# SALIDA_RF.net
KiCad netlist of a schematic drawn in Altium Designer
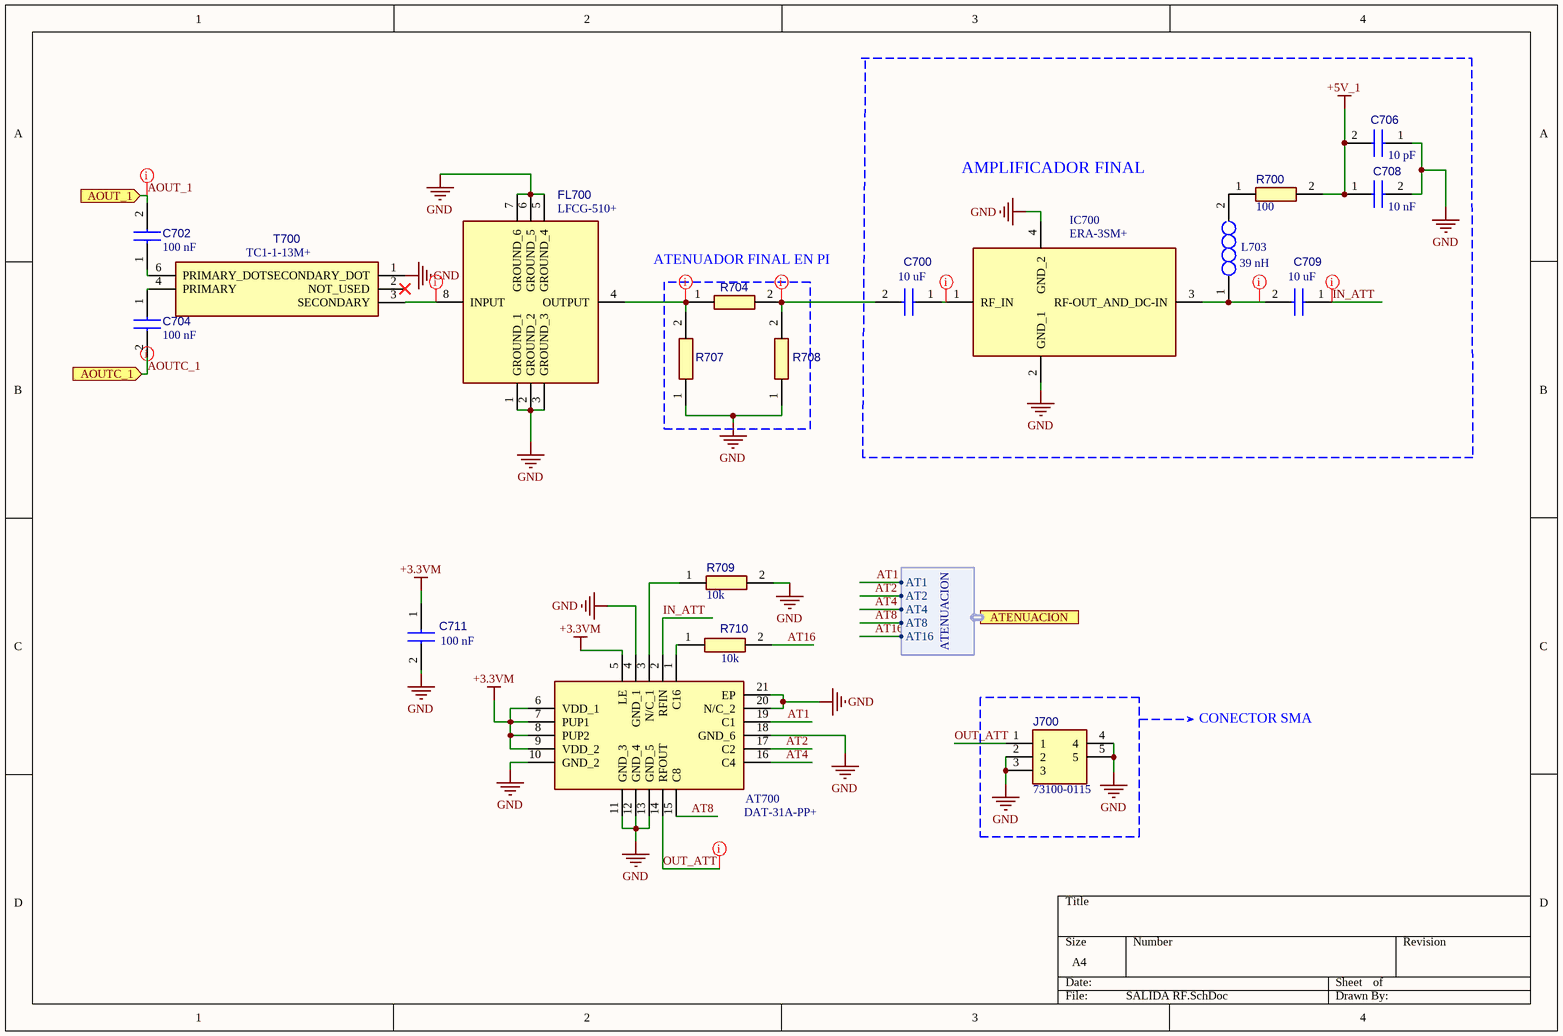
[diagram p0: SALIDA RF.SchDoc]

(export (version "E")
  (design (tool "Eeschema 10.0.6"))
  (components
    (comp (ref "AT700")
      (value "DAT-31A-PP+")
      (footprint "SamacSys:QFN50P400X400X85-21N")
      (description "Attenuator or Isolator")
      (fields (field (name "MOUSER PART NUMBER") "139-DAT-31A-PP+"))
      (libsource (lib "SamacSys") (part "DAT-31A-PP+"))
    )
    (comp (ref "C700")
      (value "10 uF")
      (footprint "SamacSys:C0603")
      (description "Capacitor")
      (fields (field (name "MANUFACTURER_PART_NUMBER") "C0603H470J5GACTU"))
      (libsource (lib "*") (part "C0603H470J5GACTU"))
    )
    (comp (ref "C702")
      (value "100 nF")
      (footprint "SamacSys:C0603")
      (description "Capacitor")
      (fields (field (name "MANUFACTURER_PART_NUMBER") "C0603H470J5GACTU"))
      (libsource (lib "*") (part "C0603H470J5GACTU"))
    )
    (comp (ref "C704")
      (value "100 nF")
      (footprint "SamacSys:C0603")
      (description "Capacitor")
      (fields (field (name "MANUFACTURER_PART_NUMBER") "C0603H470J5GACTU"))
      (libsource (lib "*") (part "C0603H470J5GACTU"))
    )
    (comp (ref "C706")
      (value "10 pF")
      (footprint "SamacSys:C0603")
      (description "Capacitor")
      (fields (field (name "MANUFACTURER_PART_NUMBER") "C0603H470J5GACTU"))
      (libsource (lib "*") (part "C0603H470J5GACTU"))
    )
    (comp (ref "C708")
      (value "10 nF")
      (footprint "SamacSys:C0603")
      (description "Capacitor")
      (fields (field (name "MANUFACTURER_PART_NUMBER") "C0603H470J5GACTU"))
      (libsource (lib "*") (part "C0603H470J5GACTU"))
    )
    (comp (ref "C709")
      (value "10 uF")
      (footprint "SamacSys:C0603")
      (description "Capacitor")
      (fields (field (name "MANUFACTURER_PART_NUMBER") "C0603H470J5GACTU"))
      (libsource (lib "*") (part "C0603H470J5GACTU"))
    )
    (comp (ref "C711")
      (value "100 nF")
      (footprint "SamacSys:C0603")
      (description "Capacitor")
      (fields (field (name "MANUFACTURER_PART_NUMBER") "C0603H470J5GACTU"))
      (libsource (lib "*") (part "C0603H470J5GACTU"))
    )
    (comp (ref "FL700")
      (value "LFCG-510+")
      (footprint "SamacSys:LFCG2000")
      (description "Filter")
      (fields
        (field (name "MANUFACTURER_PART_NUMBER") "LFCG-2000+")
        (field (name "MOUSER PART NUMBER") "139-LFCG-2000+")
      )
      (libsource (lib "*") (part "LFCG-2000+"))
    )
    (comp (ref "IC700")
      (value "ERA-3SM+")
      (footprint "SamacSys:ERA3SM")
      (description "Integrated Circuit")
      (fields (field (name "MOUSER PART NUMBER") "139-ERA-3SM"))
      (libsource (lib "*") (part "ERA-3SM+"))
    )
    (comp (ref "J700")
      (value "73100-0115")
      (footprint "SamacSys:731000115")
      (description "Connector")
      (fields (field (name "MOUSER PART NUMBER") "538-73100-0115"))
      (libsource (lib "*") (part "73100-0115"))
    )
    (comp (ref "L703")
      (value "39 nH")
      (footprint "SamacSys:INDC1608X95N")
      (description "Inductor")
      (fields
        (field (name "MANUFACTURER_PART_NUMBER") "AIML-0603-100K-T")
        (field (name "MOUSER PART NUMBER") "815-AIML-0603-100KT")
      )
      (libsource (lib "*") (part "AIML-0603-100K-T"))
    )
    (comp (ref "R700")
      (value "100")
      (footprint "SamacSys:RESC1608X55N")
      (description "Resistor")
      (fields
        (field (name "MANUFACTURER_PART_NUMBER") "CR0603-FX-1431ELF")
        (field (name "MOUSER PART NUMBER") "652-CR0603FX-1431ELF")
      )
      (libsource (lib "*") (part "CR0603-FX-1431ELF"))
    )
    (comp (ref "R704")
      (value "0")
      (footprint "SamacSys:RESC1608X55N")
      (description "Resistor")
      (fields
        (field (name "MANUFACTURER_PART_NUMBER") "CR0603-FX-1431ELF")
        (field (name "MOUSER PART NUMBER") "652-CR0603FX-1431ELF")
      )
      (libsource (lib "*") (part "CR0603-FX-1431ELF"))
    )
    (comp (ref "R707")
      (value "ATENUADOR")
      (footprint "SamacSys:RESC1608X55N")
      (description "Resistor")
      (fields
        (field (name "MANUFACTURER_PART_NUMBER") "CR0603-FX-1431ELF")
        (field (name "MOUSER PART NUMBER") "652-CR0603FX-1431ELF")
      )
      (libsource (lib "") (part "CR0603-FX-1431ELF_1"))
    )
    (comp (ref "R708")
      (value "ATENUADOR")
      (footprint "SamacSys:RESC1608X55N")
      (description "Resistor")
      (fields
        (field (name "MANUFACTURER_PART_NUMBER") "CR0603-FX-1431ELF")
        (field (name "MOUSER PART NUMBER") "652-CR0603FX-1431ELF")
      )
      (libsource (lib "") (part "CR0603-FX-1431ELF_1"))
    )
    (comp (ref "R709")
      (value "10k")
      (footprint "SamacSys:RESC1608X55N")
      (description "Resistor")
      (fields
        (field (name "MANUFACTURER_PART_NUMBER") "CR0603-FX-1431ELF")
        (field (name "MOUSER PART NUMBER") "652-CR0603FX-1431ELF")
      )
      (libsource (lib "*") (part "CR0603-FX-1431ELF"))
    )
    (comp (ref "R710")
      (value "10k")
      (footprint "SamacSys:RESC1608X55N")
      (description "Resistor")
      (fields
        (field (name "MANUFACTURER_PART_NUMBER") "CR0603-FX-1431ELF")
        (field (name "MOUSER PART NUMBER") "652-CR0603FX-1431ELF")
      )
      (libsource (lib "*") (part "CR0603-FX-1431ELF"))
    )
    (comp (ref "T700")
      (value "TC1-1-13M+")
      (footprint "SamacSys:TC414")
      (description "Transformer")
      (fields (field (name "MOUSER PART NUMBER") "139-TC1-1-13M"))
      (libsource (lib "*") (part "TC1-1-13M+"))
    )
  )
  (nets
    (net (code "2") (name "+3.3VM") (class "Default")
      (node (ref "AT700") (pin "5") (pinfunction "LE_5") (pintype "passive"))
      (node (ref "AT700") (pin "6") (pinfunction "VDD_1_6") (pintype "passive"))
      (node (ref "AT700") (pin "7") (pinfunction "PUP1_7") (pintype "passive"))
      (node (ref "AT700") (pin "8") (pinfunction "PUP2_8") (pintype "passive"))
      (node (ref "AT700") (pin "9") (pinfunction "VDD_2_9") (pintype "passive"))
      (node (ref "C711") (pin "1") (pinfunction "1_1") (pintype "passive"))
    )
    (net (code "3") (name "+5V_1") (class "Default")
      (node (ref "C706") (pin "2") (pinfunction "2_2") (pintype "passive"))
      (node (ref "C708") (pin "1") (pinfunction "1_1") (pintype "passive"))
      (node (ref "R700") (pin "2") (pinfunction "2_2") (pintype "passive"))
    )
    (net (code "4") (name "/AOUTC_1") (class "Default")
      (node (ref "C704") (pin "2") (pinfunction "2_2") (pintype "passive"))
    )
    (net (code "5") (name "/AOUT_1") (class "Default")
      (node (ref "C702") (pin "2") (pinfunction "2_2") (pintype "passive"))
    )
    (net (code "6") (name "/AT1") (class "Default")
      (node (ref "AT700") (pin "19") (pinfunction "C1_19") (pintype "passive"))
    )
    (net (code "7") (name "/AT2") (class "Default")
      (node (ref "AT700") (pin "17") (pinfunction "C2_17") (pintype "passive"))
    )
    (net (code "8") (name "/AT4") (class "Default")
      (node (ref "AT700") (pin "16") (pinfunction "C4_16") (pintype "passive"))
    )
    (net (code "9") (name "/AT8") (class "Default")
      (node (ref "AT700") (pin "15") (pinfunction "C8_15") (pintype "passive"))
    )
    (net (code "10") (name "/AT16") (class "Default")
      (node (ref "R710") (pin "2") (pinfunction "2_2") (pintype "passive"))
    )
    (net (code "11") (name "/IN_ATT") (class "Default")
      (node (ref "AT700") (pin "2") (pinfunction "RFIN_2") (pintype "passive"))
      (node (ref "C709") (pin "1") (pinfunction "1_1") (pintype "passive"))
    )
    (net (code "12") (name "/OUT_ATT") (class "Default")
      (node (ref "AT700") (pin "14") (pinfunction "RFOUT_14") (pintype "passive"))
      (node (ref "J700") (pin "1") (pinfunction "1_1") (pintype "passive"))
    )
    (net (code "14") (name "GND") (class "Default")
      (node (ref "AT700") (pin "10") (pinfunction "GND_2_10") (pintype "passive"))
      (node (ref "AT700") (pin "11") (pinfunction "GND_3_11") (pintype "passive"))
      (node (ref "AT700") (pin "12") (pinfunction "GND_4_12") (pintype "passive"))
      (node (ref "AT700") (pin "13") (pinfunction "GND_5_13") (pintype "passive"))
      (node (ref "AT700") (pin "18") (pinfunction "GND_6_18") (pintype "passive"))
      (node (ref "AT700") (pin "20") (pinfunction "N/C_2_20") (pintype "passive"))
      (node (ref "AT700") (pin "21") (pinfunction "EP_21") (pintype "passive"))
      (node (ref "AT700") (pin "4") (pinfunction "GND_1_4") (pintype "passive"))
      (node (ref "C706") (pin "1") (pinfunction "1_1") (pintype "passive"))
      (node (ref "C708") (pin "2") (pinfunction "2_2") (pintype "passive"))
      (node (ref "C711") (pin "2") (pinfunction "2_2") (pintype "passive"))
      (node (ref "FL700") (pin "1") (pinfunction "GROUND_1_1") (pintype "passive"))
      (node (ref "FL700") (pin "2") (pinfunction "GROUND_2_2") (pintype "passive"))
      (node (ref "FL700") (pin "3") (pinfunction "GROUND_3_3") (pintype "passive"))
      (node (ref "FL700") (pin "5") (pinfunction "GROUND_4_5") (pintype "passive"))
      (node (ref "FL700") (pin "6") (pinfunction "GROUND_5_6") (pintype "passive"))
      (node (ref "FL700") (pin "7") (pinfunction "GROUND_6_7") (pintype "passive"))
      (node (ref "IC700") (pin "2") (pinfunction "GND_1_2") (pintype "passive"))
      (node (ref "IC700") (pin "4") (pinfunction "GND_2_4") (pintype "passive"))
      (node (ref "J700") (pin "2") (pinfunction "2_2") (pintype "passive"))
      (node (ref "J700") (pin "3") (pinfunction "3_3") (pintype "passive"))
      (node (ref "J700") (pin "4") (pinfunction "4_4") (pintype "passive"))
      (node (ref "J700") (pin "5") (pinfunction "5_5") (pintype "passive"))
      (node (ref "R707") (pin "1") (pinfunction "1_1") (pintype "passive"))
      (node (ref "R708") (pin "1") (pinfunction "1_1") (pintype "passive"))
      (node (ref "R709") (pin "2") (pinfunction "2_2") (pintype "passive"))
      (node (ref "T700") (pin "1") (pinfunction "SECONDARY_DOT_1") (pintype "passive"))
    )
    (net (code "15") (name "Net-(AT700-C16)") (class "Default")
      (node (ref "AT700") (pin "1") (pinfunction "C16_1") (pintype "passive"))
      (node (ref "R710") (pin "1") (pinfunction "1_1") (pintype "passive"))
    )
    (net (code "16") (name "Net-(AT700-N{slash}C_1)") (class "Default")
      (node (ref "AT700") (pin "3") (pinfunction "N/C_1_3") (pintype "passive"))
      (node (ref "R709") (pin "1") (pinfunction "1_1") (pintype "passive"))
    )
    (net (code "17") (name "Net-(C700-Pad2)") (class "Default")
      (node (ref "C700") (pin "2") (pinfunction "2_2") (pintype "passive"))
      (node (ref "R704") (pin "2") (pinfunction "2_2") (pintype "passive"))
      (node (ref "R708") (pin "2") (pinfunction "2_2") (pintype "passive"))
    )
    (net (code "18") (name "Net-(FL700-INPUT)") (class "Default")
      (node (ref "FL700") (pin "8") (pinfunction "INPUT_8") (pintype "passive"))
      (node (ref "T700") (pin "3") (pinfunction "SECONDARY_3") (pintype "passive"))
    )
    (net (code "19") (name "Net-(FL700-OUTPUT)") (class "Default")
      (node (ref "FL700") (pin "4") (pinfunction "OUTPUT_4") (pintype "passive"))
      (node (ref "R704") (pin "1") (pinfunction "1_1") (pintype "passive"))
      (node (ref "R707") (pin "2") (pinfunction "2_2") (pintype "passive"))
    )
    (net (code "20") (name "Net-(IC700-RF-OUT_AND_DC-IN)") (class "Default")
      (node (ref "C709") (pin "2") (pinfunction "2_2") (pintype "passive"))
      (node (ref "IC700") (pin "3") (pinfunction "RF-OUT_AND_DC-IN_3") (pintype "passive"))
      (node (ref "L703") (pin "1") (pinfunction "1_1") (pintype "passive"))
    )
    (net (code "21") (name "Net-(IC700-RF_IN)") (class "Default")
      (node (ref "C700") (pin "1") (pinfunction "1_1") (pintype "passive"))
      (node (ref "IC700") (pin "1") (pinfunction "RF_IN_1") (pintype "passive"))
    )
    (net (code "22") (name "Net-(L703-Pad2)") (class "Default")
      (node (ref "L703") (pin "2") (pinfunction "2_2") (pintype "passive"))
      (node (ref "R700") (pin "1") (pinfunction "1_1") (pintype "passive"))
    )
    (net (code "23") (name "Net-(T700-PRIMARY)") (class "Default")
      (node (ref "C704") (pin "1") (pinfunction "1_1") (pintype "passive"))
      (node (ref "T700") (pin "4") (pinfunction "PRIMARY_4") (pintype "passive"))
    )
    (net (code "24") (name "Net-(T700-PRIMARY_DOT)") (class "Default")
      (node (ref "C702") (pin "1") (pinfunction "1_1") (pintype "passive"))
      (node (ref "T700") (pin "6") (pinfunction "PRIMARY_DOT_6") (pintype "passive"))
    )
    (net (code "25") (name "unconnected-(T700-NOT_USED-Pad2)") (class "Default")
      (node (ref "T700") (pin "2") (pinfunction "NOT_USED_2") (pintype "passive+no_connect"))
    )
  )
)
